# 3_FPGA.net
KiCad netlist of a schematic drawn in Altium Designer
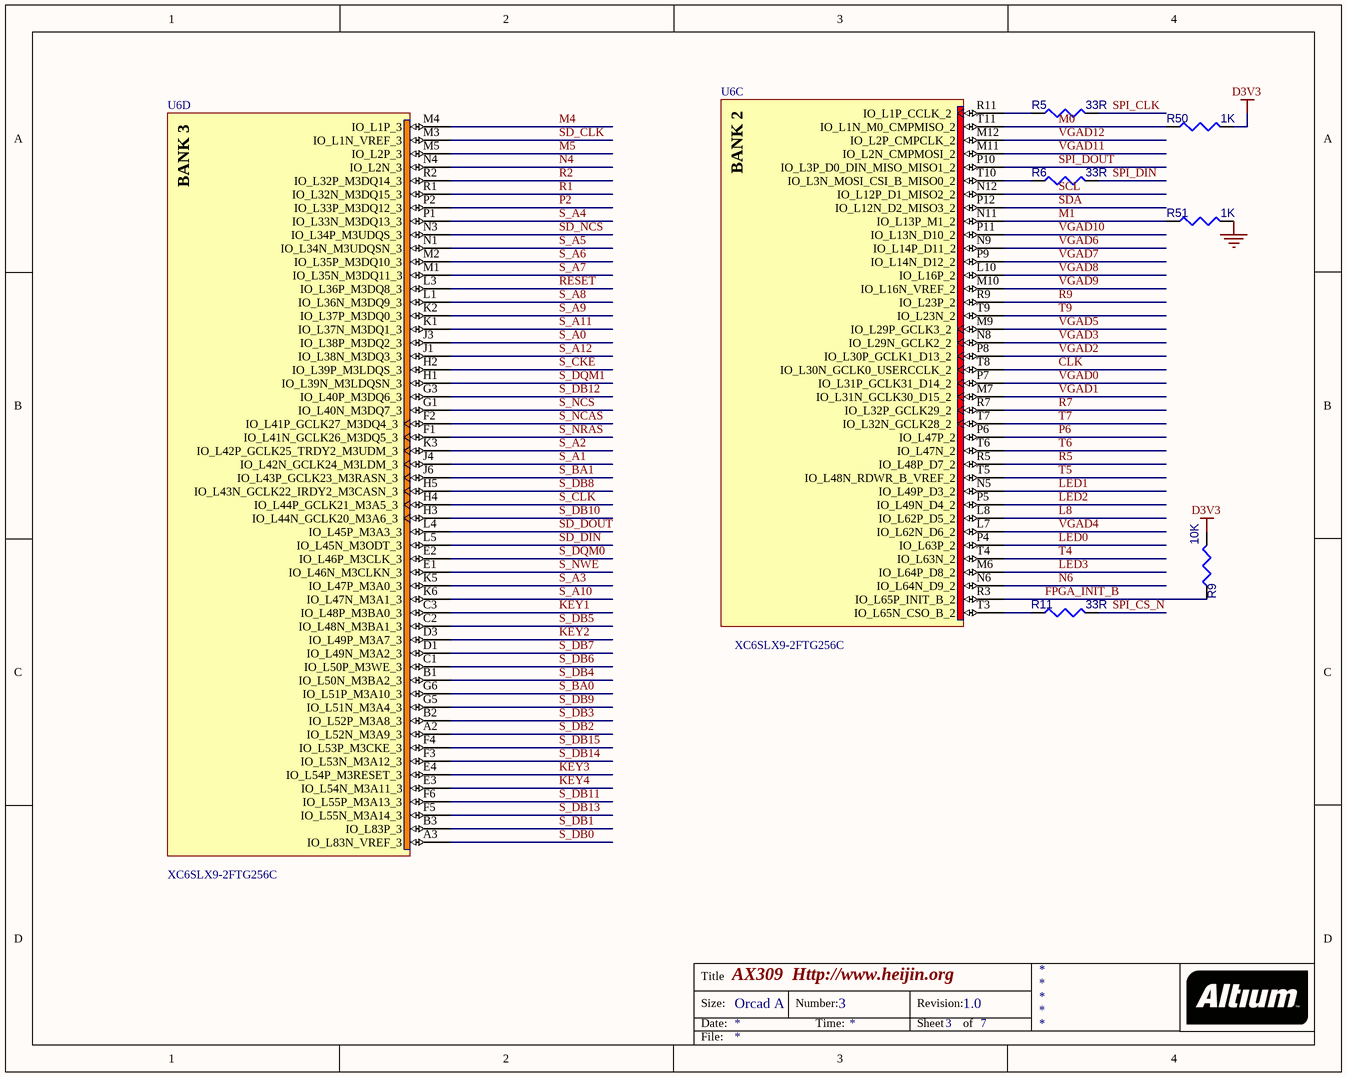
[diagram p0: 3_FPGA.SchDoc]

(export (version "E")
  (design (tool "Eeschema 10.0.6"))
  (components
    (comp (ref "R5") (value "33R") (footprint "0603") (libsource (lib "*") (part "R_Dup3")))
    (comp (ref "R6") (value "33R") (footprint "0603") (libsource (lib "*") (part "R_Dup3")))
    (comp (ref "R9") (value "10K") (footprint "0603") (libsource (lib "*") (part "R_Dup1")))
    (comp (ref "R11") (value "33R") (footprint "0603") (libsource (lib "*") (part "R_Dup3")))
    (comp (ref "R50") (value "1K") (footprint "0603") (libsource (lib "*") (part "R")))
    (comp (ref "R51") (value "1K") (footprint "0603") (libsource (lib "*") (part "R")))
    (comp (ref "U6")
      (value "XC6SLX9-2FTG256C")
      (footprint "FTG256")
      (libsource (lib "Xilinx Spartan-6") (part "XC6SLX9-2FTG256C"))
    )
  )
  (nets
    (net (code "1") (name "/CLK") (class "Default")
      (node (ref "U6") (pin "T8") (pinfunction "IO_L30N_GCLK0_USERCCLK_2_T8") (pintype "bidirectional"))
    )
    (net (code "2") (name "/FPGA_INIT_B") (class "Default")
      (node (ref "R9") (pin "1") (pinfunction "1_1") (pintype "passive"))
      (node (ref "U6") (pin "R3") (pinfunction "IO_L65P_INIT_B_2_R3") (pintype "bidirectional"))
    )
    (net (code "3") (name "/KEY1") (class "Default")
      (node (ref "U6") (pin "C3") (pinfunction "IO_L48P_M3BA0_3_C3") (pintype "bidirectional"))
    )
    (net (code "4") (name "/KEY2") (class "Default")
      (node (ref "U6") (pin "D3") (pinfunction "IO_L49P_M3A7_3_D3") (pintype "bidirectional"))
    )
    (net (code "5") (name "/KEY3") (class "Default")
      (node (ref "U6") (pin "E4") (pinfunction "IO_L54P_M3RESET_3_E4") (pintype "bidirectional"))
    )
    (net (code "6") (name "/KEY4") (class "Default")
      (node (ref "U6") (pin "E3") (pinfunction "IO_L54N_M3A11_3_E3") (pintype "bidirectional"))
    )
    (net (code "7") (name "/L8") (class "Default")
      (node (ref "U6") (pin "L8") (pinfunction "IO_L62P_D5_2_L8") (pintype "bidirectional"))
    )
    (net (code "8") (name "/LED0") (class "Default")
      (node (ref "U6") (pin "P4") (pinfunction "IO_L63P_2_P4") (pintype "bidirectional"))
    )
    (net (code "9") (name "/LED1") (class "Default")
      (node (ref "U6") (pin "N5") (pinfunction "IO_L49P_D3_2_N5") (pintype "bidirectional"))
    )
    (net (code "10") (name "/LED2") (class "Default")
      (node (ref "U6") (pin "P5") (pinfunction "IO_L49N_D4_2_P5") (pintype "bidirectional"))
    )
    (net (code "11") (name "/LED3") (class "Default")
      (node (ref "U6") (pin "M6") (pinfunction "IO_L64P_D8_2_M6") (pintype "bidirectional"))
    )
    (net (code "12") (name "/M0") (class "Default")
      (node (ref "R50") (pin "1") (pinfunction "1_1") (pintype "passive"))
      (node (ref "U6") (pin "T11") (pinfunction "IO_L1N_M0_CMPMISO_2_T11") (pintype "bidirectional"))
    )
    (net (code "13") (name "/M1") (class "Default")
      (node (ref "R51") (pin "1") (pinfunction "1_1") (pintype "passive"))
      (node (ref "U6") (pin "N11") (pinfunction "IO_L13P_M1_2_N11") (pintype "bidirectional"))
    )
    (net (code "14") (name "/M4") (class "Default")
      (node (ref "U6") (pin "M4") (pinfunction "IO_L1P_3_M4") (pintype "bidirectional"))
    )
    (net (code "15") (name "/M5") (class "Default")
      (node (ref "U6") (pin "M5") (pinfunction "IO_L2P_3_M5") (pintype "bidirectional"))
    )
    (net (code "16") (name "/N4") (class "Default")
      (node (ref "U6") (pin "N4") (pinfunction "IO_L2N_3_N4") (pintype "bidirectional"))
    )
    (net (code "17") (name "/N6") (class "Default")
      (node (ref "U6") (pin "N6") (pinfunction "IO_L64N_D9_2_N6") (pintype "bidirectional"))
    )
    (net (code "18") (name "/P2") (class "Default")
      (node (ref "U6") (pin "P2") (pinfunction "IO_L33P_M3DQ12_3_P2") (pintype "bidirectional"))
    )
    (net (code "19") (name "/P6") (class "Default")
      (node (ref "U6") (pin "P6") (pinfunction "IO_L47P_2_P6") (pintype "bidirectional"))
    )
    (net (code "20") (name "/R1") (class "Default")
      (node (ref "U6") (pin "R1") (pinfunction "IO_L32N_M3DQ15_3_R1") (pintype "bidirectional"))
    )
    (net (code "21") (name "/R2") (class "Default")
      (node (ref "U6") (pin "R2") (pinfunction "IO_L32P_M3DQ14_3_R2") (pintype "bidirectional"))
    )
    (net (code "22") (name "/R5") (class "Default")
      (node (ref "U6") (pin "R5") (pinfunction "IO_L48P_D7_2_R5") (pintype "bidirectional"))
    )
    (net (code "23") (name "/R7") (class "Default")
      (node (ref "U6") (pin "R7") (pinfunction "IO_L32P_GCLK29_2_R7") (pintype "bidirectional"))
    )
    (net (code "24") (name "/R9") (class "Default")
      (node (ref "U6") (pin "R9") (pinfunction "IO_L23P_2_R9") (pintype "bidirectional"))
    )
    (net (code "25") (name "/RESET") (class "Default")
      (node (ref "U6") (pin "L3") (pinfunction "IO_L36P_M3DQ8_3_L3") (pintype "bidirectional"))
    )
    (net (code "26") (name "/SCL") (class "Default")
      (node (ref "U6") (pin "N12") (pinfunction "IO_L12P_D1_MISO2_2_N12") (pintype "bidirectional"))
    )
    (net (code "27") (name "/SDA") (class "Default")
      (node (ref "U6") (pin "P12") (pinfunction "IO_L12N_D2_MISO3_2_P12") (pintype "bidirectional"))
    )
    (net (code "28") (name "/SD_CLK") (class "Default")
      (node (ref "U6") (pin "M3") (pinfunction "IO_L1N_VREF_3_M3") (pintype "bidirectional"))
    )
    (net (code "29") (name "/SD_DIN") (class "Default")
      (node (ref "U6") (pin "L5") (pinfunction "IO_L45N_M3ODT_3_L5") (pintype "bidirectional"))
    )
    (net (code "30") (name "/SD_DOUT") (class "Default")
      (node (ref "U6") (pin "L4") (pinfunction "IO_L45P_M3A3_3_L4") (pintype "bidirectional"))
    )
    (net (code "31") (name "/SD_NCS") (class "Default")
      (node (ref "U6") (pin "N3") (pinfunction "IO_L34P_M3UDQS_3_N3") (pintype "bidirectional"))
    )
    (net (code "32") (name "/SPI_CLK") (class "Default")
      (node (ref "R5") (pin "2") (pinfunction "2_2") (pintype "passive"))
    )
    (net (code "33") (name "/SPI_CS_N") (class "Default")
      (node (ref "R11") (pin "2") (pinfunction "2_2") (pintype "passive"))
    )
    (net (code "34") (name "/SPI_DIN") (class "Default")
      (node (ref "R6") (pin "2") (pinfunction "2_2") (pintype "passive"))
    )
    (net (code "35") (name "/SPI_DOUT") (class "Default")
      (node (ref "U6") (pin "P10") (pinfunction "IO_L3P_D0_DIN_MISO_MISO1_2_P10") (pintype "bidirectional"))
    )
    (net (code "36") (name "/S_A0") (class "Default")
      (node (ref "U6") (pin "J3") (pinfunction "IO_L38P_M3DQ2_3_J3") (pintype "bidirectional"))
    )
    (net (code "37") (name "/S_A1") (class "Default")
      (node (ref "U6") (pin "J4") (pinfunction "IO_L42N_GCLK24_M3LDM_3_J4") (pintype "bidirectional"))
    )
    (net (code "38") (name "/S_A2") (class "Default")
      (node (ref "U6") (pin "K3") (pinfunction "IO_L42P_GCLK25_TRDY2_M3UDM_3_K3") (pintype "bidirectional"))
    )
    (net (code "39") (name "/S_A3") (class "Default")
      (node (ref "U6") (pin "K5") (pinfunction "IO_L47P_M3A0_3_K5") (pintype "bidirectional"))
    )
    (net (code "40") (name "/S_A4") (class "Default")
      (node (ref "U6") (pin "P1") (pinfunction "IO_L33N_M3DQ13_3_P1") (pintype "bidirectional"))
    )
    (net (code "41") (name "/S_A5") (class "Default")
      (node (ref "U6") (pin "N1") (pinfunction "IO_L34N_M3UDQSN_3_N1") (pintype "bidirectional"))
    )
    (net (code "42") (name "/S_A6") (class "Default")
      (node (ref "U6") (pin "M2") (pinfunction "IO_L35P_M3DQ10_3_M2") (pintype "bidirectional"))
    )
    (net (code "43") (name "/S_A7") (class "Default")
      (node (ref "U6") (pin "M1") (pinfunction "IO_L35N_M3DQ11_3_M1") (pintype "bidirectional"))
    )
    (net (code "44") (name "/S_A8") (class "Default")
      (node (ref "U6") (pin "L1") (pinfunction "IO_L36N_M3DQ9_3_L1") (pintype "bidirectional"))
    )
    (net (code "45") (name "/S_A9") (class "Default")
      (node (ref "U6") (pin "K2") (pinfunction "IO_L37P_M3DQ0_3_K2") (pintype "bidirectional"))
    )
    (net (code "46") (name "/S_A10") (class "Default")
      (node (ref "U6") (pin "K6") (pinfunction "IO_L47N_M3A1_3_K6") (pintype "bidirectional"))
    )
    (net (code "47") (name "/S_A11") (class "Default")
      (node (ref "U6") (pin "K1") (pinfunction "IO_L37N_M3DQ1_3_K1") (pintype "bidirectional"))
    )
    (net (code "48") (name "/S_A12") (class "Default")
      (node (ref "U6") (pin "J1") (pinfunction "IO_L38N_M3DQ3_3_J1") (pintype "bidirectional"))
    )
    (net (code "49") (name "/S_BA0") (class "Default")
      (node (ref "U6") (pin "G6") (pinfunction "IO_L51P_M3A10_3_G6") (pintype "bidirectional"))
    )
    (net (code "50") (name "/S_BA1") (class "Default")
      (node (ref "U6") (pin "J6") (pinfunction "IO_L43P_GCLK23_M3RASN_3_J6") (pintype "bidirectional"))
    )
    (net (code "51") (name "/S_CKE") (class "Default")
      (node (ref "U6") (pin "H2") (pinfunction "IO_L39P_M3LDQS_3_H2") (pintype "bidirectional"))
    )
    (net (code "52") (name "/S_CLK") (class "Default")
      (node (ref "U6") (pin "H4") (pinfunction "IO_L44P_GCLK21_M3A5_3_H4") (pintype "bidirectional"))
    )
    (net (code "53") (name "/S_DB0") (class "Default")
      (node (ref "U6") (pin "A3") (pinfunction "IO_L83N_VREF_3_A3") (pintype "bidirectional"))
    )
    (net (code "54") (name "/S_DB1") (class "Default")
      (node (ref "U6") (pin "B3") (pinfunction "IO_L83P_3_B3") (pintype "bidirectional"))
    )
    (net (code "55") (name "/S_DB2") (class "Default")
      (node (ref "U6") (pin "A2") (pinfunction "IO_L52N_M3A9_3_A2") (pintype "bidirectional"))
    )
    (net (code "56") (name "/S_DB3") (class "Default")
      (node (ref "U6") (pin "B2") (pinfunction "IO_L52P_M3A8_3_B2") (pintype "bidirectional"))
    )
    (net (code "57") (name "/S_DB4") (class "Default")
      (node (ref "U6") (pin "B1") (pinfunction "IO_L50N_M3BA2_3_B1") (pintype "bidirectional"))
    )
    (net (code "58") (name "/S_DB5") (class "Default")
      (node (ref "U6") (pin "C2") (pinfunction "IO_L48N_M3BA1_3_C2") (pintype "bidirectional"))
    )
    (net (code "59") (name "/S_DB6") (class "Default")
      (node (ref "U6") (pin "C1") (pinfunction "IO_L50P_M3WE_3_C1") (pintype "bidirectional"))
    )
    (net (code "60") (name "/S_DB7") (class "Default")
      (node (ref "U6") (pin "D1") (pinfunction "IO_L49N_M3A2_3_D1") (pintype "bidirectional"))
    )
    (net (code "61") (name "/S_DB8") (class "Default")
      (node (ref "U6") (pin "H5") (pinfunction "IO_L43N_GCLK22_IRDY2_M3CASN_3_H5") (pintype "bidirectional"))
    )
    (net (code "62") (name "/S_DB9") (class "Default")
      (node (ref "U6") (pin "G5") (pinfunction "IO_L51N_M3A4_3_G5") (pintype "bidirectional"))
    )
    (net (code "63") (name "/S_DB10") (class "Default")
      (node (ref "U6") (pin "H3") (pinfunction "IO_L44N_GCLK20_M3A6_3_H3") (pintype "bidirectional"))
    )
    (net (code "64") (name "/S_DB11") (class "Default")
      (node (ref "U6") (pin "F6") (pinfunction "IO_L55P_M3A13_3_F6") (pintype "bidirectional"))
    )
    (net (code "65") (name "/S_DB12") (class "Default")
      (node (ref "U6") (pin "G3") (pinfunction "IO_L40P_M3DQ6_3_G3") (pintype "bidirectional"))
    )
    (net (code "66") (name "/S_DB13") (class "Default")
      (node (ref "U6") (pin "F5") (pinfunction "IO_L55N_M3A14_3_F5") (pintype "bidirectional"))
    )
    (net (code "67") (name "/S_DB14") (class "Default")
      (node (ref "U6") (pin "F3") (pinfunction "IO_L53N_M3A12_3_F3") (pintype "bidirectional"))
    )
    (net (code "68") (name "/S_DB15") (class "Default")
      (node (ref "U6") (pin "F4") (pinfunction "IO_L53P_M3CKE_3_F4") (pintype "bidirectional"))
    )
    (net (code "69") (name "/S_DQM0") (class "Default")
      (node (ref "U6") (pin "E2") (pinfunction "IO_L46P_M3CLK_3_E2") (pintype "bidirectional"))
    )
    (net (code "70") (name "/S_DQM1") (class "Default")
      (node (ref "U6") (pin "H1") (pinfunction "IO_L39N_M3LDQSN_3_H1") (pintype "bidirectional"))
    )
    (net (code "71") (name "/S_NCAS") (class "Default")
      (node (ref "U6") (pin "F2") (pinfunction "IO_L41P_GCLK27_M3DQ4_3_F2") (pintype "bidirectional"))
    )
    (net (code "72") (name "/S_NCS") (class "Default")
      (node (ref "U6") (pin "G1") (pinfunction "IO_L40N_M3DQ7_3_G1") (pintype "bidirectional"))
    )
    (net (code "73") (name "/S_NRAS") (class "Default")
      (node (ref "U6") (pin "F1") (pinfunction "IO_L41N_GCLK26_M3DQ5_3_F1") (pintype "bidirectional"))
    )
    (net (code "74") (name "/S_NWE") (class "Default")
      (node (ref "U6") (pin "E1") (pinfunction "IO_L46N_M3CLKN_3_E1") (pintype "bidirectional"))
    )
    (net (code "75") (name "/T4") (class "Default")
      (node (ref "U6") (pin "T4") (pinfunction "IO_L63N_2_T4") (pintype "bidirectional"))
    )
    (net (code "76") (name "/T5") (class "Default")
      (node (ref "U6") (pin "T5") (pinfunction "IO_L48N_RDWR_B_VREF_2_T5") (pintype "bidirectional"))
    )
    (net (code "77") (name "/T6") (class "Default")
      (node (ref "U6") (pin "T6") (pinfunction "IO_L47N_2_T6") (pintype "bidirectional"))
    )
    (net (code "78") (name "/T7") (class "Default")
      (node (ref "U6") (pin "T7") (pinfunction "IO_L32N_GCLK28_2_T7") (pintype "bidirectional"))
    )
    (net (code "79") (name "/T9") (class "Default")
      (node (ref "U6") (pin "T9") (pinfunction "IO_L23N_2_T9") (pintype "bidirectional"))
    )
    (net (code "80") (name "/VGAD0") (class "Default")
      (node (ref "U6") (pin "P7") (pinfunction "IO_L31P_GCLK31_D14_2_P7") (pintype "bidirectional"))
    )
    (net (code "81") (name "/VGAD1") (class "Default")
      (node (ref "U6") (pin "M7") (pinfunction "IO_L31N_GCLK30_D15_2_M7") (pintype "bidirectional"))
    )
    (net (code "82") (name "/VGAD2") (class "Default")
      (node (ref "U6") (pin "P8") (pinfunction "IO_L30P_GCLK1_D13_2_P8") (pintype "bidirectional"))
    )
    (net (code "83") (name "/VGAD3") (class "Default")
      (node (ref "U6") (pin "N8") (pinfunction "IO_L29N_GCLK2_2_N8") (pintype "bidirectional"))
    )
    (net (code "84") (name "/VGAD4") (class "Default")
      (node (ref "U6") (pin "L7") (pinfunction "IO_L62N_D6_2_L7") (pintype "bidirectional"))
    )
    (net (code "85") (name "/VGAD5") (class "Default")
      (node (ref "U6") (pin "M9") (pinfunction "IO_L29P_GCLK3_2_M9") (pintype "bidirectional"))
    )
    (net (code "86") (name "/VGAD6") (class "Default")
      (node (ref "U6") (pin "N9") (pinfunction "IO_L14P_D11_2_N9") (pintype "bidirectional"))
    )
    (net (code "87") (name "/VGAD7") (class "Default")
      (node (ref "U6") (pin "P9") (pinfunction "IO_L14N_D12_2_P9") (pintype "bidirectional"))
    )
    (net (code "88") (name "/VGAD8") (class "Default")
      (node (ref "U6") (pin "L10") (pinfunction "IO_L16P_2_L10") (pintype "bidirectional"))
    )
    (net (code "89") (name "/VGAD9") (class "Default")
      (node (ref "U6") (pin "M10") (pinfunction "IO_L16N_VREF_2_M10") (pintype "bidirectional"))
    )
    (net (code "90") (name "/VGAD10") (class "Default")
      (node (ref "U6") (pin "P11") (pinfunction "IO_L13N_D10_2_P11") (pintype "bidirectional"))
    )
    (net (code "91") (name "/VGAD11") (class "Default")
      (node (ref "U6") (pin "M11") (pinfunction "IO_L2N_CMPMOSI_2_M11") (pintype "bidirectional"))
    )
    (net (code "92") (name "/VGAD12") (class "Default")
      (node (ref "U6") (pin "M12") (pinfunction "IO_L2P_CMPCLK_2_M12") (pintype "bidirectional"))
    )
    (net (code "93") (name "D3V3") (class "Default")
      (node (ref "R50") (pin "2") (pinfunction "2_2") (pintype "passive"))
      (node (ref "R9") (pin "2") (pinfunction "2_2") (pintype "passive"))
    )
    (net (code "94") (name "GND") (class "Default")
      (node (ref "R51") (pin "2") (pinfunction "2_2") (pintype "passive"))
    )
    (net (code "95") (name "Net-(U6C-IO_L1P_CCLK_2)") (class "Default")
      (node (ref "R5") (pin "1") (pinfunction "1_1") (pintype "passive"))
      (node (ref "U6") (pin "R11") (pinfunction "IO_L1P_CCLK_2_R11") (pintype "bidirectional"))
    )
    (net (code "96") (name "Net-(U6C-IO_L3N_MOSI_CSI_B_MISO0_2)") (class "Default")
      (node (ref "R6") (pin "1") (pinfunction "1_1") (pintype "passive"))
      (node (ref "U6") (pin "T10") (pinfunction "IO_L3N_MOSI_CSI_B_MISO0_2_T10") (pintype "bidirectional"))
    )
    (net (code "97") (name "Net-(U6C-IO_L65N_CSO_B_2)") (class "Default")
      (node (ref "R11") (pin "1") (pinfunction "1_1") (pintype "passive"))
      (node (ref "U6") (pin "T3") (pinfunction "IO_L65N_CSO_B_2_T3") (pintype "bidirectional"))
    )
  )
)
